# buck_regulator.net
KiCad netlist of a schematic drawn in EAGLE
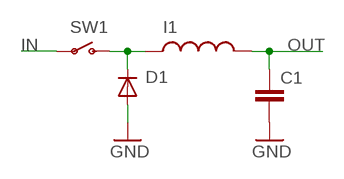
[diagram p0: schematic, sheet 1]

(export (version "E")
  (design (tool "Eeschema 10.0.6"))
  (components
    (comp (ref "C1")
      (value "CAP0402-CAP")
      (footprint "eagle-import:0402-CAP")
      (libsource (lib "eagle-import") (part "CAP0402-CAP"))
    )
    (comp (ref "D1")
      (value "DIODE1N4148")
      (footprint "eagle-import:DIODE-1N4148")
      (libsource (lib "eagle-import") (part "DIODE1N4148"))
    )
    (comp (ref "I1")
      (value "INDUCTOR")
      (footprint "eagle-import:BOURNES_E12")
      (libsource (lib "eagle-import") (part "INDUCTOR"))
    )
    (comp (ref "SW1")
      (value "SWITCH_SPST")
      (footprint "eagle-import:SPST_SMT_19192")
      (libsource (lib "eagle-import") (part "SWITCH_SPST"))
    )
  )
  (nets
    (net (code "1") (name "/IN") (class "Default")
      (node (ref "SW1") (pin "B") (pinfunction "P_B") (pintype "passive"))
    )
    (net (code "2") (name "/OUT") (class "Default")
      (node (ref "C1") (pin "1") (pinfunction "1_1") (pintype "passive"))
      (node (ref "I1") (pin "P$2") (pinfunction "2_P$2") (pintype "passive"))
    )
    (net (code "3") (name "GND") (class "Default")
      (node (ref "C1") (pin "2") (pinfunction "2_2") (pintype "passive"))
      (node (ref "D1") (pin "A") (pinfunction "A_A") (pintype "passive"))
    )
    (net (code "4") (name "Net-(I1-1)") (class "Default")
      (node (ref "D1") (pin "C") (pinfunction "C_C") (pintype "passive"))
      (node (ref "I1") (pin "P$1") (pinfunction "1_P$1") (pintype "passive"))
      (node (ref "SW1") (pin "C") (pinfunction "S_C") (pintype "passive"))
    )
  )
)
